# ART-Pi_Memory.net
KiCad netlist of a schematic drawn in Altium Designer
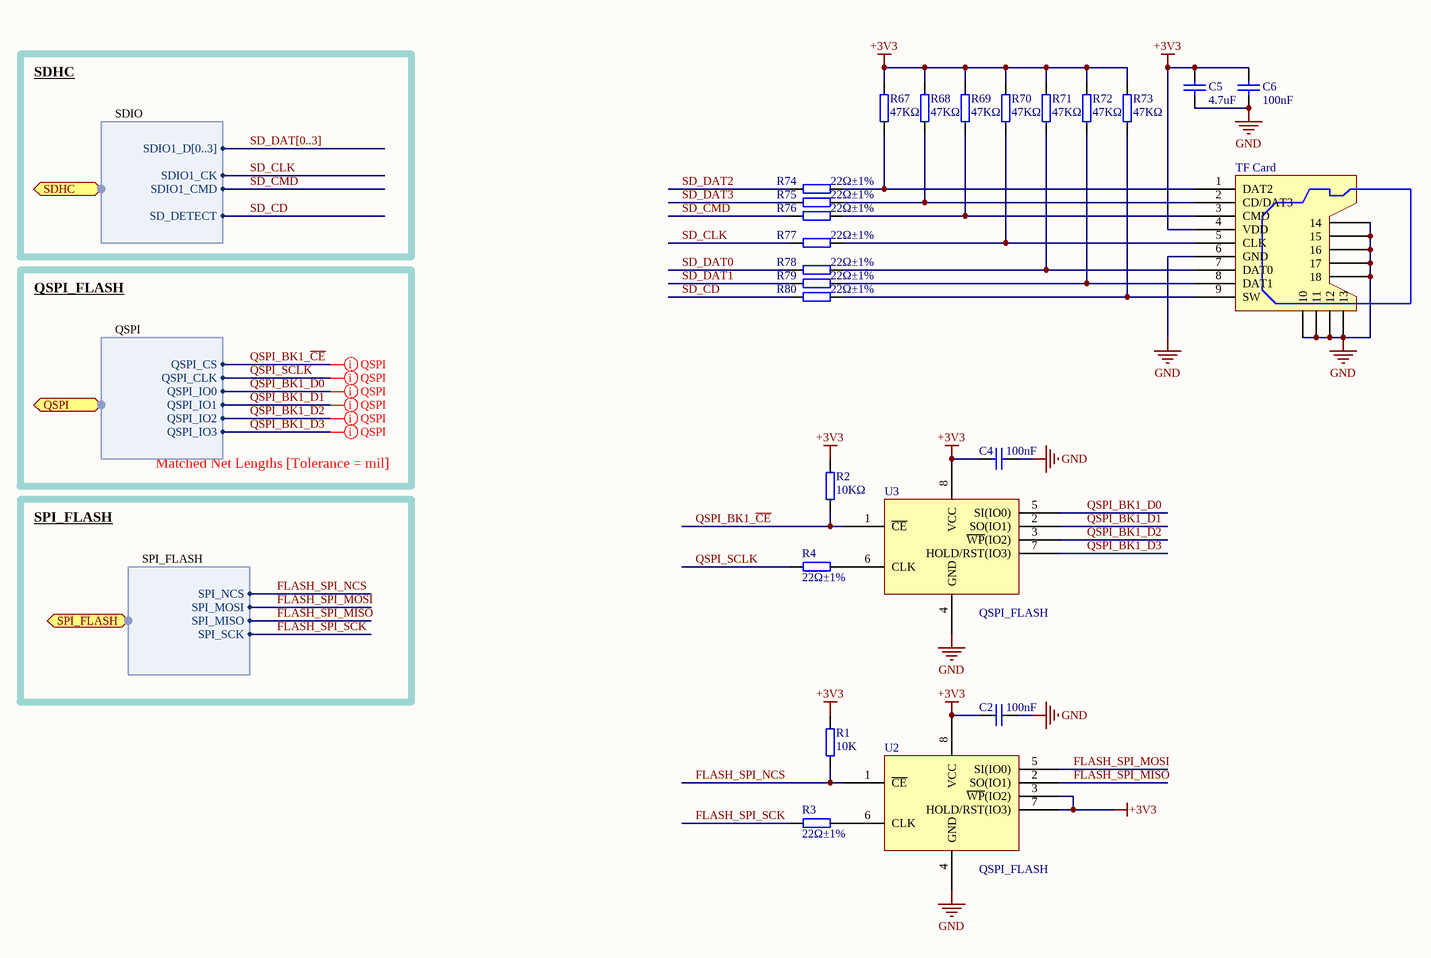
[diagram p0: ART-Pi_Memory.SchDoc]

(export (version "E")
  (design (tool "Eeschema 10.0.6"))
  (components
    (comp (ref "C2")
      (value "100nF")
      (footprint "0402_C")
      (description "Capacitor")
      (fields (field (name "PUBLISHER") "Altium Limited"))
      (libsource (lib "ART-Pi_STM32H750_COPY") (part "Cap"))
    )
    (comp (ref "C4")
      (value "100nF")
      (footprint "0402_C")
      (description "Capacitor")
      (fields (field (name "PUBLISHER") "Altium Limited"))
      (libsource (lib "ART-Pi_STM32H750_COPY") (part "Cap"))
    )
    (comp (ref "C5")
      (value "4.7uF")
      (footprint "0402_C")
      (description "Capacitor")
      (fields (field (name "PUBLISHER") "Altium Limited"))
      (libsource (lib "ART-Pi_STM32H750_COPY") (part "Cap"))
    )
    (comp (ref "C6")
      (value "100nF")
      (footprint "0402_C")
      (description "Capacitor")
      (fields (field (name "PUBLISHER") "Altium Limited"))
      (libsource (lib "ART-Pi_STM32H750_COPY") (part "Cap"))
    )
    (comp (ref "R1")
      (value "10K")
      (footprint "0402_R")
      (description "Resister")
      (libsource (lib "ART-Pi_STM32H750_COPY") (part "Res"))
    )
    (comp (ref "R2")
      (value "10KΩ")
      (footprint "0402_R")
      (description "Resister")
      (libsource (lib "ART-Pi_STM32H750_COPY") (part "Res"))
    )
    (comp (ref "R3")
      (value "22Ω±1%")
      (footprint "0402_R")
      (description "Resister")
      (libsource (lib "ART-Pi_STM32H750_COPY") (part "Res"))
    )
    (comp (ref "R4")
      (value "22Ω±1%")
      (footprint "0402_R")
      (description "Resister")
      (libsource (lib "ART-Pi_STM32H750_COPY") (part "Res"))
    )
    (comp (ref "R67")
      (value "47KΩ")
      (footprint "0402_R")
      (description "Resister")
      (libsource (lib "ART-Pi_STM32H750_COPY") (part "Res"))
    )
    (comp (ref "R68")
      (value "47KΩ")
      (footprint "0402_R")
      (description "Resister")
      (libsource (lib "ART-Pi_STM32H750_COPY") (part "Res"))
    )
    (comp (ref "R69")
      (value "47KΩ")
      (footprint "0402_R")
      (description "Resister")
      (libsource (lib "ART-Pi_STM32H750_COPY") (part "Res"))
    )
    (comp (ref "R70")
      (value "47KΩ")
      (footprint "0402_R")
      (description "Resister")
      (libsource (lib "ART-Pi_STM32H750_COPY") (part "Res"))
    )
    (comp (ref "R71")
      (value "47KΩ")
      (footprint "0402_R")
      (description "Resister")
      (libsource (lib "ART-Pi_STM32H750_COPY") (part "Res"))
    )
    (comp (ref "R72")
      (value "47KΩ")
      (footprint "0402_R")
      (description "Resister")
      (libsource (lib "ART-Pi_STM32H750_COPY") (part "Res"))
    )
    (comp (ref "R73")
      (value "47KΩ")
      (footprint "0402_R")
      (description "Resister")
      (libsource (lib "ART-Pi_STM32H750_COPY") (part "Res"))
    )
    (comp (ref "R74")
      (value "22Ω±1%")
      (footprint "0402_R")
      (description "Resister")
      (libsource (lib "ART-Pi_STM32H750_COPY") (part "Res"))
    )
    (comp (ref "R75")
      (value "22Ω±1%")
      (footprint "0402_R")
      (description "Resister")
      (libsource (lib "ART-Pi_STM32H750_COPY") (part "Res"))
    )
    (comp (ref "R76")
      (value "22Ω±1%")
      (footprint "0402_R")
      (description "Resister")
      (libsource (lib "ART-Pi_STM32H750_COPY") (part "Res"))
    )
    (comp (ref "R77")
      (value "22Ω±1%")
      (footprint "0402_R")
      (description "Resister")
      (libsource (lib "ART-Pi_STM32H750_COPY") (part "Res"))
    )
    (comp (ref "R78")
      (value "22Ω±1%")
      (footprint "0402_R")
      (description "Resister")
      (libsource (lib "ART-Pi_STM32H750_COPY") (part "Res"))
    )
    (comp (ref "R79")
      (value "22Ω±1%")
      (footprint "0402_R")
      (description "Resister")
      (libsource (lib "ART-Pi_STM32H750_COPY") (part "Res"))
    )
    (comp (ref "R80")
      (value "22Ω±1%")
      (footprint "0402_R")
      (description "Resister")
      (libsource (lib "ART-Pi_STM32H750_COPY") (part "Res"))
    )
    (comp (ref "TF Card")
      (value "microSD")
      (footprint "TF-SMD_TF-110")
      (libsource (lib "ART-Pi_STM32H750_COPY") (part "microSD"))
    )
    (comp (ref "U2")
      (value "QSPI_FLASH")
      (footprint "SOIC_8")
      (description "W25Q128")
      (libsource (lib "ART-Pi_STM32H750_COPY") (part "W25Q128"))
    )
    (comp (ref "U3")
      (value "QSPI_FLASH")
      (footprint "SOIC_8")
      (description "W25Q128")
      (libsource (lib "ART-Pi_STM32H750_COPY") (part "W25Q128"))
    )
  )
  (nets
    (net (code "3") (name "+3V3") (class "Default")
      (node (ref "C2") (pin "2") (pinfunction "2_2") (pintype "passive"))
      (node (ref "C4") (pin "2") (pinfunction "2_2") (pintype "passive"))
      (node (ref "C5") (pin "2") (pinfunction "2_2") (pintype "passive"))
      (node (ref "C6") (pin "2") (pinfunction "2_2") (pintype "passive"))
      (node (ref "R1") (pin "1") (pinfunction "1_1") (pintype "passive"))
      (node (ref "R2") (pin "1") (pinfunction "1_1") (pintype "passive"))
      (node (ref "R67") (pin "1") (pinfunction "1_1") (pintype "passive"))
      (node (ref "R68") (pin "1") (pinfunction "1_1") (pintype "passive"))
      (node (ref "R69") (pin "1") (pinfunction "1_1") (pintype "passive"))
      (node (ref "R70") (pin "1") (pinfunction "1_1") (pintype "passive"))
      (node (ref "R71") (pin "1") (pinfunction "1_1") (pintype "passive"))
      (node (ref "R72") (pin "1") (pinfunction "1_1") (pintype "passive"))
      (node (ref "R73") (pin "1") (pinfunction "1_1") (pintype "passive"))
      (node (ref "TF Card") (pin "4") (pinfunction "VDD_4") (pintype "passive"))
      (node (ref "U2") (pin "3") (pinfunction "~{WP}(IO2)_3") (pintype "passive"))
      (node (ref "U2") (pin "7") (pinfunction "HOLD/RST(IO3)_7") (pintype "power_in"))
      (node (ref "U2") (pin "8") (pinfunction "VCC_8") (pintype "passive"))
      (node (ref "U3") (pin "8") (pinfunction "VCC_8") (pintype "passive"))
    )
    (net (code "4") (name "/FLASH_SPI_MISO") (class "Default")
      (node (ref "U2") (pin "2") (pinfunction "SO(IO1)_2") (pintype "passive"))
    )
    (net (code "5") (name "/FLASH_SPI_MOSI") (class "Default")
      (node (ref "U2") (pin "5") (pinfunction "SI(IO0)_5") (pintype "power_in"))
    )
    (net (code "6") (name "/FLASH_SPI_NCS") (class "Default")
      (node (ref "R1") (pin "2") (pinfunction "2_2") (pintype "passive"))
      (node (ref "U2") (pin "1") (pinfunction "~{CE}_1") (pintype "passive"))
    )
    (net (code "7") (name "/FLASH_SPI_SCK") (class "Default")
      (node (ref "R3") (pin "2") (pinfunction "2_2") (pintype "passive"))
    )
    (net (code "8") (name "/QSPI_BK1_D0") (class "Default")
      (node (ref "U3") (pin "5") (pinfunction "SI(IO0)_5") (pintype "power_in"))
    )
    (net (code "9") (name "/QSPI_BK1_D1") (class "Default")
      (node (ref "U3") (pin "2") (pinfunction "SO(IO1)_2") (pintype "passive"))
    )
    (net (code "10") (name "/QSPI_BK1_D2") (class "Default")
      (node (ref "U3") (pin "3") (pinfunction "~{WP}(IO2)_3") (pintype "passive"))
    )
    (net (code "11") (name "/QSPI_BK1_D3") (class "Default")
      (node (ref "U3") (pin "7") (pinfunction "HOLD/RST(IO3)_7") (pintype "power_in"))
    )
    (net (code "12") (name "/QSPI_BK1_~{CE}") (class "Default")
      (node (ref "R2") (pin "2") (pinfunction "2_2") (pintype "passive"))
      (node (ref "U3") (pin "1") (pinfunction "~{CE}_1") (pintype "passive"))
    )
    (net (code "13") (name "/QSPI_SCLK") (class "Default")
      (node (ref "R4") (pin "2") (pinfunction "2_2") (pintype "passive"))
    )
    (net (code "15") (name "/SD_CD") (class "Default")
      (node (ref "R80") (pin "2") (pinfunction "2_2") (pintype "passive"))
    )
    (net (code "16") (name "/SD_CLK") (class "Default")
      (node (ref "R77") (pin "2") (pinfunction "2_2") (pintype "passive"))
    )
    (net (code "17") (name "/SD_CMD") (class "Default")
      (node (ref "R76") (pin "2") (pinfunction "2_2") (pintype "passive"))
    )
    (net (code "18") (name "/SD_DAT0") (class "Default")
      (node (ref "R78") (pin "2") (pinfunction "2_2") (pintype "passive"))
    )
    (net (code "19") (name "/SD_DAT1") (class "Default")
      (node (ref "R79") (pin "2") (pinfunction "2_2") (pintype "passive"))
    )
    (net (code "20") (name "/SD_DAT2") (class "Default")
      (node (ref "R74") (pin "2") (pinfunction "2_2") (pintype "passive"))
    )
    (net (code "21") (name "/SD_DAT3") (class "Default")
      (node (ref "R75") (pin "2") (pinfunction "2_2") (pintype "passive"))
    )
    (net (code "24") (name "GND") (class "Default")
      (node (ref "C2") (pin "1") (pinfunction "1_1") (pintype "passive"))
      (node (ref "C4") (pin "1") (pinfunction "1_1") (pintype "passive"))
      (node (ref "C5") (pin "1") (pinfunction "1_1") (pintype "passive"))
      (node (ref "C6") (pin "1") (pinfunction "1_1") (pintype "passive"))
      (node (ref "TF Card") (pin "10") (pinfunction "10_10") (pintype "passive"))
      (node (ref "TF Card") (pin "11") (pinfunction "11_11") (pintype "passive"))
      (node (ref "TF Card") (pin "12") (pinfunction "12_12") (pintype "passive"))
      (node (ref "TF Card") (pin "13") (pinfunction "13_13") (pintype "passive"))
      (node (ref "TF Card") (pin "14") (pinfunction "14_14") (pintype "passive"))
      (node (ref "TF Card") (pin "15") (pinfunction "15_15") (pintype "passive"))
      (node (ref "TF Card") (pin "16") (pinfunction "16_16") (pintype "passive"))
      (node (ref "TF Card") (pin "17") (pinfunction "17_17") (pintype "passive"))
      (node (ref "TF Card") (pin "18") (pinfunction "18_18") (pintype "passive"))
      (node (ref "TF Card") (pin "6") (pinfunction "GND_6") (pintype "passive"))
      (node (ref "U2") (pin "4") (pinfunction "GND_4") (pintype "passive"))
      (node (ref "U3") (pin "4") (pinfunction "GND_4") (pintype "passive"))
    )
    (net (code "25") (name "Net-(TF Card-CD{slash}DAT3)") (class "Default")
      (node (ref "R68") (pin "2") (pinfunction "2_2") (pintype "passive"))
      (node (ref "R75") (pin "1") (pinfunction "1_1") (pintype "passive"))
      (node (ref "TF Card") (pin "2") (pinfunction "CD/DAT3_2") (pintype "passive"))
    )
    (net (code "26") (name "Net-(TF Card-CLK)") (class "Default")
      (node (ref "R70") (pin "2") (pinfunction "2_2") (pintype "passive"))
      (node (ref "R77") (pin "1") (pinfunction "1_1") (pintype "passive"))
      (node (ref "TF Card") (pin "5") (pinfunction "CLK_5") (pintype "passive"))
    )
    (net (code "27") (name "Net-(TF Card-CMD)") (class "Default")
      (node (ref "R69") (pin "2") (pinfunction "2_2") (pintype "passive"))
      (node (ref "R76") (pin "1") (pinfunction "1_1") (pintype "passive"))
      (node (ref "TF Card") (pin "3") (pinfunction "CMD_3") (pintype "passive"))
    )
    (net (code "28") (name "Net-(TF Card-DAT0)") (class "Default")
      (node (ref "R71") (pin "2") (pinfunction "2_2") (pintype "passive"))
      (node (ref "R78") (pin "1") (pinfunction "1_1") (pintype "passive"))
      (node (ref "TF Card") (pin "7") (pinfunction "DAT0_7") (pintype "passive"))
    )
    (net (code "29") (name "Net-(TF Card-DAT1)") (class "Default")
      (node (ref "R72") (pin "2") (pinfunction "2_2") (pintype "passive"))
      (node (ref "R79") (pin "1") (pinfunction "1_1") (pintype "passive"))
      (node (ref "TF Card") (pin "8") (pinfunction "DAT1_8") (pintype "passive"))
    )
    (net (code "30") (name "Net-(TF Card-DAT2)") (class "Default")
      (node (ref "R67") (pin "2") (pinfunction "2_2") (pintype "passive"))
      (node (ref "R74") (pin "1") (pinfunction "1_1") (pintype "passive"))
      (node (ref "TF Card") (pin "1") (pinfunction "DAT2_1") (pintype "passive"))
    )
    (net (code "31") (name "Net-(TF Card-SW)") (class "Default")
      (node (ref "R73") (pin "2") (pinfunction "2_2") (pintype "passive"))
      (node (ref "R80") (pin "1") (pinfunction "1_1") (pintype "passive"))
      (node (ref "TF Card") (pin "9") (pinfunction "SW_9") (pintype "passive"))
    )
    (net (code "32") (name "Net-(U2-CLK)") (class "Default")
      (node (ref "R3") (pin "1") (pinfunction "1_1") (pintype "passive"))
      (node (ref "U2") (pin "6") (pinfunction "CLK_6") (pintype "passive"))
    )
    (net (code "33") (name "Net-(U3-CLK)") (class "Default")
      (node (ref "R4") (pin "1") (pinfunction "1_1") (pintype "passive"))
      (node (ref "U3") (pin "6") (pinfunction "CLK_6") (pintype "passive"))
    )
  )
)
